# Interfaz_Keyence_Di_metro.net
KiCad netlist of a schematic drawn in EAGLE
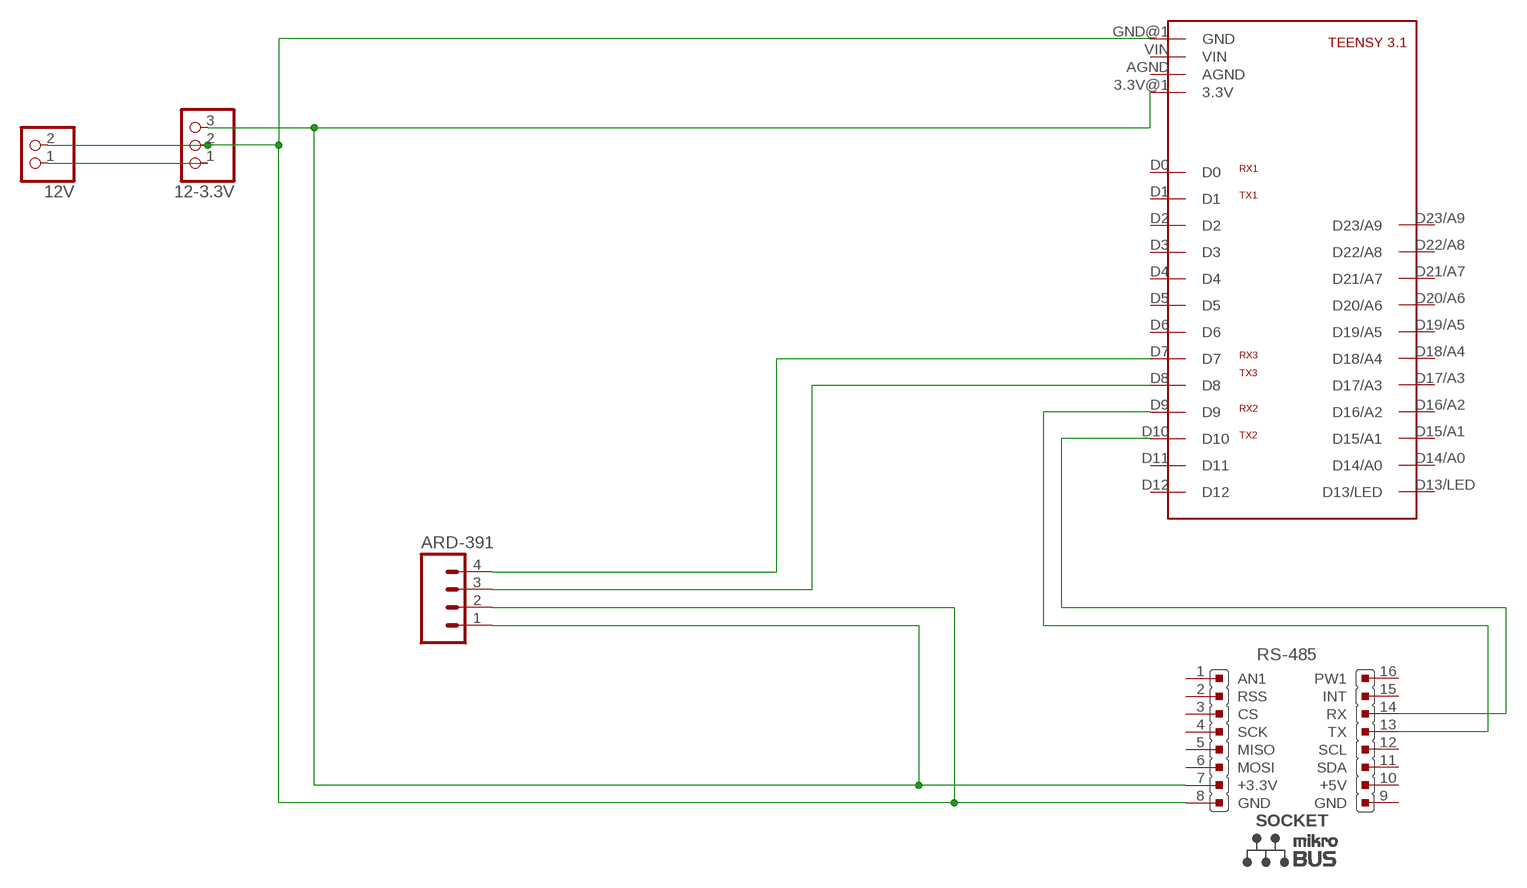
[diagram p0: schematic, sheet 1]

(export (version "E")
  (design (tool "Eeschema 10.0.6"))
  (components
    (comp (ref "12-3.3V")
      (value "HEADER-1X3ROUND")
      (footprint "eagle-import:1X03_ROUND")
      (libsource (lib "eagle-import") (part "HEADER-1X3ROUND"))
    )
    (comp (ref "12V")
      (value "HEADER-1X2ROUND")
      (footprint "eagle-import:1X02_ROUND")
      (libsource (lib "eagle-import") (part "HEADER-1X2ROUND"))
    )
    (comp (ref "ARD-391")
      (value "M04NO_SILK_ALL_ROUND")
      (footprint "eagle-import:1X04_NO_SILK_ALL_ROUND")
      (libsource (lib "eagle-import") (part "M04NO_SILK_ALL_ROUND"))
    )
    (comp (ref "RS-485")
      (value "MIKROBUS")
      (footprint "eagle-import:MIKROBUS")
      (libsource (lib "eagle-import") (part "MIKROBUS"))
    )
    (comp (ref "U$1")
      (value "TEENSY3.1_FRONT")
      (footprint "eagle-import:TEENSY3.1_ALL")
      (libsource (lib "eagle-import") (part "TEENSY3.1_FRONT"))
    )
  )
  (nets
    (net (code "1") (name "Net-(12-3.3V-Pad1)") (class "Default")
      (node (ref "12-3.3V") (pin "1") (pinfunction "1_1") (pintype "passive"))
      (node (ref "12V") (pin "1") (pinfunction "1_1") (pintype "passive"))
    )
    (net (code "2") (name "Net-(ARD-391-Pad3)") (class "Default")
      (node (ref "ARD-391") (pin "3") (pinfunction "3_3") (pintype "passive"))
      (node (ref "U$1") (pin "D8") (pinfunction "D8_D8") (pintype "bidirectional"))
    )
    (net (code "3") (name "Net-(ARD-391-Pad4)") (class "Default")
      (node (ref "ARD-391") (pin "4") (pinfunction "4_4") (pintype "passive"))
      (node (ref "U$1") (pin "D7") (pinfunction "D7_D7") (pintype "bidirectional"))
    )
    (net (code "4") (name "Net-(RS-485-+3.3V)") (class "Default")
      (node (ref "12-3.3V") (pin "3") (pinfunction "3_3") (pintype "passive"))
      (node (ref "ARD-391") (pin "1") (pinfunction "1_1") (pintype "passive"))
      (node (ref "RS-485") (pin "7") (pinfunction "+3.3V_7") (pintype "passive"))
      (node (ref "U$1") (pin "3.3V@1") (pinfunction "3.3V_3.3V@1") (pintype "bidirectional"))
    )
    (net (code "5") (name "Net-(RS-485-RX)") (class "Default")
      (node (ref "RS-485") (pin "14") (pinfunction "RX_14") (pintype "bidirectional"))
      (node (ref "U$1") (pin "D10") (pinfunction "D10_D10") (pintype "bidirectional"))
    )
    (net (code "6") (name "Net-(RS-485-TX)") (class "Default")
      (node (ref "RS-485") (pin "13") (pinfunction "TX_13") (pintype "bidirectional"))
      (node (ref "U$1") (pin "D9") (pinfunction "D9_D9") (pintype "bidirectional"))
    )
    (net (code "7") (name "Net-(U$1-GND)") (class "Default")
      (node (ref "12-3.3V") (pin "2") (pinfunction "2_2") (pintype "passive"))
      (node (ref "12V") (pin "2") (pinfunction "2_2") (pintype "passive"))
      (node (ref "ARD-391") (pin "2") (pinfunction "2_2") (pintype "passive"))
      (node (ref "RS-485") (pin "8") (pinfunction "GND_8") (pintype "passive"))
      (node (ref "U$1") (pin "GND@1") (pinfunction "GND_GND@1") (pintype "bidirectional"))
    )
    (net (code "8") (name "unconnected-(RS-485-+5V-Pad10)") (class "Default")
      (node (ref "RS-485") (pin "10") (pinfunction "+5V_10") (pintype "passive"))
    )
    (net (code "9") (name "unconnected-(RS-485-AN1-Pad1)") (class "Default")
      (node (ref "RS-485") (pin "1") (pinfunction "AN1_1") (pintype "bidirectional"))
    )
    (net (code "10") (name "unconnected-(RS-485-CS-Pad3)") (class "Default")
      (node (ref "RS-485") (pin "3") (pinfunction "CS_3") (pintype "bidirectional"))
    )
    (net (code "11") (name "unconnected-(RS-485-GND-Pad9)") (class "Default")
      (node (ref "RS-485") (pin "9") (pinfunction "GND_9") (pintype "passive"))
    )
    (net (code "12") (name "unconnected-(RS-485-INT-Pad15)") (class "Default")
      (node (ref "RS-485") (pin "15") (pinfunction "INT_15") (pintype "bidirectional"))
    )
    (net (code "13") (name "unconnected-(RS-485-MISO-Pad5)") (class "Default")
      (node (ref "RS-485") (pin "5") (pinfunction "MISO_5") (pintype "bidirectional"))
    )
    (net (code "14") (name "unconnected-(RS-485-MOSI-Pad6)") (class "Default")
      (node (ref "RS-485") (pin "6") (pinfunction "MOSI_6") (pintype "bidirectional"))
    )
    (net (code "15") (name "unconnected-(RS-485-PW1-Pad16)") (class "Default")
      (node (ref "RS-485") (pin "16") (pinfunction "PW1_16") (pintype "bidirectional"))
    )
    (net (code "16") (name "unconnected-(RS-485-RSS-Pad2)") (class "Default")
      (node (ref "RS-485") (pin "2") (pinfunction "RSS_2") (pintype "bidirectional"))
    )
    (net (code "17") (name "unconnected-(RS-485-SCK-Pad4)") (class "Default")
      (node (ref "RS-485") (pin "4") (pinfunction "SCK_4") (pintype "bidirectional"))
    )
    (net (code "18") (name "unconnected-(RS-485-SCL-Pad12)") (class "Default")
      (node (ref "RS-485") (pin "12") (pinfunction "SCL_12") (pintype "bidirectional"))
    )
    (net (code "19") (name "unconnected-(RS-485-SDA-Pad11)") (class "Default")
      (node (ref "RS-485") (pin "11") (pinfunction "SDA_11") (pintype "bidirectional"))
    )
    (net (code "20") (name "unconnected-(U$1-PadAGND)") (class "Default")
      (node (ref "U$1") (pin "AGND") (pinfunction "AGND_AGND") (pintype "bidirectional"))
    )
    (net (code "21") (name "unconnected-(U$1-PadD0)") (class "Default")
      (node (ref "U$1") (pin "D0") (pinfunction "D0_D0") (pintype "bidirectional"))
    )
    (net (code "22") (name "unconnected-(U$1-PadD1)") (class "Default")
      (node (ref "U$1") (pin "D1") (pinfunction "D1_D1") (pintype "bidirectional"))
    )
    (net (code "23") (name "unconnected-(U$1-PadD2)") (class "Default")
      (node (ref "U$1") (pin "D2") (pinfunction "D2_D2") (pintype "bidirectional"))
    )
    (net (code "24") (name "unconnected-(U$1-PadD3)") (class "Default")
      (node (ref "U$1") (pin "D3") (pinfunction "D3_D3") (pintype "bidirectional"))
    )
    (net (code "25") (name "unconnected-(U$1-PadD4)") (class "Default")
      (node (ref "U$1") (pin "D4") (pinfunction "D4_D4") (pintype "bidirectional"))
    )
    (net (code "26") (name "unconnected-(U$1-PadD5)") (class "Default")
      (node (ref "U$1") (pin "D5") (pinfunction "D5_D5") (pintype "bidirectional"))
    )
    (net (code "27") (name "unconnected-(U$1-PadD6)") (class "Default")
      (node (ref "U$1") (pin "D6") (pinfunction "D6_D6") (pintype "bidirectional"))
    )
    (net (code "28") (name "unconnected-(U$1-PadD11)") (class "Default")
      (node (ref "U$1") (pin "D11") (pinfunction "D11_D11") (pintype "bidirectional"))
    )
    (net (code "29") (name "unconnected-(U$1-PadD12)") (class "Default")
      (node (ref "U$1") (pin "D12") (pinfunction "D12_D12") (pintype "bidirectional"))
    )
    (net (code "30") (name "unconnected-(U$1-PadD13{slash}LED)") (class "Default")
      (node (ref "U$1") (pin "D13/LED") (pinfunction "D13/LED_D13/LED") (pintype "bidirectional"))
    )
    (net (code "31") (name "unconnected-(U$1-PadD14{slash}A0)") (class "Default")
      (node (ref "U$1") (pin "D14/A0") (pinfunction "D14/A0_D14/A0") (pintype "bidirectional"))
    )
    (net (code "32") (name "unconnected-(U$1-PadD15{slash}A1)") (class "Default")
      (node (ref "U$1") (pin "D15/A1") (pinfunction "D15/A1_D15/A1") (pintype "bidirectional"))
    )
    (net (code "33") (name "unconnected-(U$1-PadD16{slash}A2)") (class "Default")
      (node (ref "U$1") (pin "D16/A2") (pinfunction "D16/A2_D16/A2") (pintype "bidirectional"))
    )
    (net (code "34") (name "unconnected-(U$1-PadD17{slash}A3)") (class "Default")
      (node (ref "U$1") (pin "D17/A3") (pinfunction "D17/A3_D17/A3") (pintype "bidirectional"))
    )
    (net (code "35") (name "unconnected-(U$1-PadD18{slash}A4)") (class "Default")
      (node (ref "U$1") (pin "D18/A4") (pinfunction "D18/A4_D18/A4") (pintype "bidirectional"))
    )
    (net (code "36") (name "unconnected-(U$1-PadD19{slash}A5)") (class "Default")
      (node (ref "U$1") (pin "D19/A5") (pinfunction "D19/A5_D19/A5") (pintype "bidirectional"))
    )
    (net (code "37") (name "unconnected-(U$1-PadD20{slash}A6)") (class "Default")
      (node (ref "U$1") (pin "D20/A6") (pinfunction "D20/A6_D20/A6") (pintype "bidirectional"))
    )
    (net (code "38") (name "unconnected-(U$1-PadD21{slash}A7)") (class "Default")
      (node (ref "U$1") (pin "D21/A7") (pinfunction "D21/A7_D21/A7") (pintype "bidirectional"))
    )
    (net (code "39") (name "unconnected-(U$1-PadD22{slash}A8)") (class "Default")
      (node (ref "U$1") (pin "D22/A8") (pinfunction "D22/A8_D22/A8") (pintype "bidirectional"))
    )
    (net (code "40") (name "unconnected-(U$1-PadD23{slash}A9)") (class "Default")
      (node (ref "U$1") (pin "D23/A9") (pinfunction "D23/A9_D23/A9") (pintype "bidirectional"))
    )
    (net (code "41") (name "unconnected-(U$1-PadVIN)") (class "Default")
      (node (ref "U$1") (pin "VIN") (pinfunction "VIN_VIN") (pintype "bidirectional"))
    )
  )
)
